# Relay_IO.net
KiCad netlist of a schematic drawn in Altium Designer
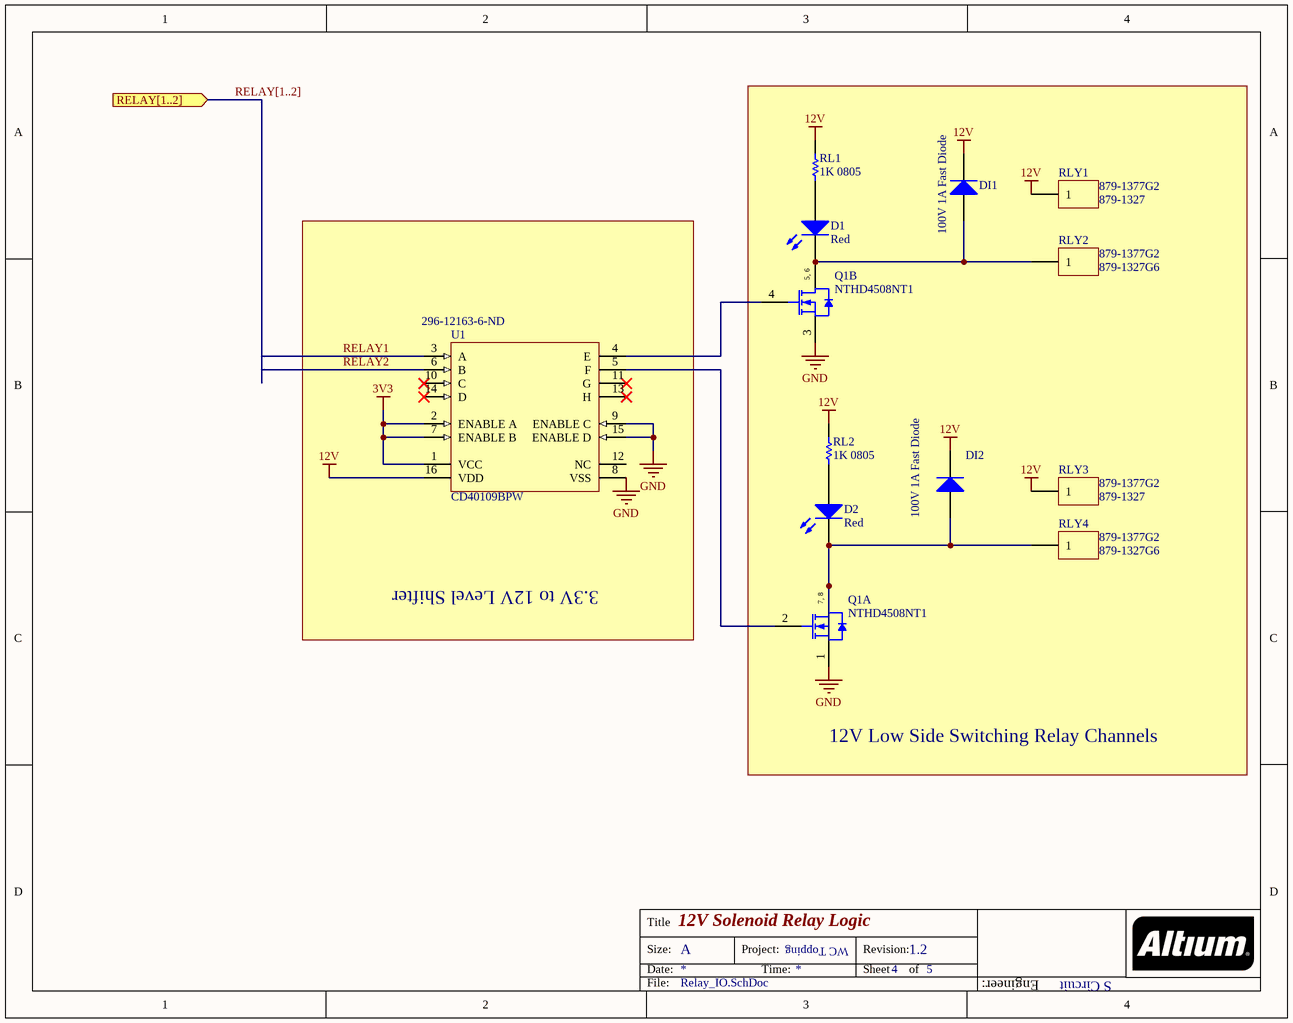
[diagram p0: Relay_IO.SchDoc]

(export (version "E")
  (design (tool "Eeschema 10.0.6"))
  (components
    (comp (ref "D1")
      (value "LED Red")
      (footprint "0603_A")
      (description "SMD mono-color Chip LED, WL-SMCW, Red")
      (fields
        (field (name "COLOR") "Red")
        (field (name "MANUFACTURER") "Wurth Electronics Inc")
        (field (name "MANUFACTURER PART NUMBER") "150060RS75000")
      )
      (libsource (lib "ICEdigikey") (part "LED_Red0603"))
    )
    (comp (ref "D2")
      (value "LED Red")
      (footprint "0603_A")
      (description "SMD mono-color Chip LED, WL-SMCW, Red")
      (fields
        (field (name "COLOR") "Red")
        (field (name "MANUFACTURER") "Wurth Electronics Inc")
        (field (name "MANUFACTURER PART NUMBER") "150060RS75000")
      )
      (libsource (lib "ICEdigikey") (part "LED_Red0603"))
    )
    (comp (ref "DI1")
      (value "100V 1A Fast Diode")
      (footprint "DO-35")
      (description "High Conductance Fast Diode")
      (fields
        (field (name "MANUFACTURER") "ON Semiconductor")
        (field (name "MANUFACTURER PART NUMBER") "MUR110RLG")
      )
      (libsource (lib "ICEdigikey") (part "Diode 1N4148"))
    )
    (comp (ref "DI2")
      (value "100V 1A Fast Diode")
      (footprint "DO-35")
      (description "High Conductance Fast Diode")
      (fields
        (field (name "MANUFACTURER") "ON Semiconductor")
        (field (name "MANUFACTURER PART NUMBER") "MUR110RLG")
      )
      (libsource (lib "ICEdigikey") (part "Diode 1N4148"))
    )
    (comp (ref "Q1")
      (value "NTHD4508NT1")
      (footprint "ONSC-CHIPFET-8-1206A-03_S2_V")
      (description "Power MOSFET, 20 V, 4.1 A, Dual N-Channel, 8-Pin CHIPFET, Tape and Reel")
      (fields
        (field (name "MANUFACTURER") "On Semiconductor")
        (field (name "MANUFACTURER PART NUMBER") "NTHD4508NT1G")
      )
      (libsource (lib "ICEdigikey") (part "NTHD4508NT1"))
    )
    (comp (ref "RL1")
      (value "1K 0805")
      (footprint "0805_L")
      (fields
        (field (name "MANUFACTURER") "Panasonic Electronic Components")
        (field (name "MANUFACTURER PART NUMBER") "ERJ-6GEYJ102V")
        (field (name "TOLERANCE") "±5%")
      )
      (libsource (lib "ICEdigikey") (part "Res1K_0805"))
    )
    (comp (ref "RL2")
      (value "1K 0805")
      (footprint "0805_L")
      (fields
        (field (name "MANUFACTURER") "Panasonic Electronic Components")
        (field (name "MANUFACTURER PART NUMBER") "ERJ-6GEYJ102V")
        (field (name "TOLERANCE") "±5%")
      )
      (libsource (lib "ICEdigikey") (part "Res1K_0805"))
    )
    (comp (ref "RLY1")
      (value "Anderson-1Pin RED_PCB_RHT")
      (footprint "Anderson_Red_RHT_BOT")
      (description "1 pin Anderson")
      (fields
        (field (name "MANUFACTURER") "Anderson Power Products (APP)")
        (field (name "MANUFACTURER PART NUMBER") "1377G1, 1377G2, 1327-BK,137G6-BK")
        (field (name "SUPPLIER PART NUMBER 1") "879-1377G2")
        (field (name "SUPPLIER PART NUMBER 2") "879-1327")
      )
      (libsource (lib "WCT") (part "Anderson-1Pin RED_PCB_RHT"))
    )
    (comp (ref "RLY2")
      (value "Anderson-1Pin BLK_PCB_RHT")
      (footprint "Anderson_BLK_RHT_BOT")
      (description "1 pin Anderson")
      (fields
        (field (name "MANUFACTURER") "Anderson Power Products (APP)")
        (field (name "MANUFACTURER PART NUMBER") "1377G1, 1377G2, 1327-BK,137G6-BK")
        (field (name "SUPPLIER PART NUMBER 1") "879-1377G2")
        (field (name "SUPPLIER PART NUMBER 2") "879-1327G6")
      )
      (libsource (lib "WCT") (part "Anderson-1Pin BLK_PCB_RHT"))
    )
    (comp (ref "RLY3")
      (value "Anderson-1Pin RED_PCB_RHT")
      (footprint "Anderson_Red_RHT_BOT")
      (description "1 pin Anderson")
      (fields
        (field (name "MANUFACTURER") "Anderson Power Products (APP)")
        (field (name "MANUFACTURER PART NUMBER") "1377G1, 1377G2, 1327-BK,137G6-BK")
        (field (name "SUPPLIER PART NUMBER 1") "879-1377G2")
        (field (name "SUPPLIER PART NUMBER 2") "879-1327")
      )
      (libsource (lib "WCT") (part "Anderson-1Pin RED_PCB_RHT"))
    )
    (comp (ref "RLY4")
      (value "Anderson-1Pin BLK_PCB_RHT")
      (footprint "Anderson_BLK_RHT_BOT")
      (description "1 pin Anderson")
      (fields
        (field (name "MANUFACTURER") "Anderson Power Products (APP)")
        (field (name "MANUFACTURER PART NUMBER") "1377G1, 1377G2, 1327-BK,137G6-BK")
        (field (name "SUPPLIER PART NUMBER 1") "879-1377G2")
        (field (name "SUPPLIER PART NUMBER 2") "879-1327G6")
      )
      (libsource (lib "WCT") (part "Anderson-1Pin BLK_PCB_RHT"))
    )
    (comp (ref "U1")
      (value "CD40109BPW")
      (footprint "PW0016A_M")
      (fields
        (field (name "MANUFACTURER") "Texas Instruments")
        (field (name "SUPPLIER PART NUMBER 1") "296-12163-6-ND")
        (field (name "MANUFACTURER PART NUMBER") "CD40109BPWR")
      )
      (libsource (lib "Altium Content Vault") (part "CMP-1527-00010-2"))
    )
  )
  (nets
    (net (code "1") (name "/RELAY1") (class "Default")
      (node (ref "U1") (pin "3") (pinfunction "A_3") (pintype "input"))
    )
    (net (code "2") (name "/RELAY2") (class "Default")
      (node (ref "U1") (pin "6") (pinfunction "B_6") (pintype "input"))
    )
    (net (code "4") (name "3V3") (class "Default")
      (node (ref "U1") (pin "1") (pinfunction "VCC_1") (pintype "power_in"))
      (node (ref "U1") (pin "2") (pinfunction "ENABLE_A_2") (pintype "input"))
      (node (ref "U1") (pin "7") (pinfunction "ENABLE_B_7") (pintype "input"))
    )
    (net (code "5") (name "12V") (class "Default")
      (node (ref "DI1") (pin "2") (pinfunction "K_2") (pintype "passive"))
      (node (ref "DI2") (pin "2") (pinfunction "K_2") (pintype "passive"))
      (node (ref "RL1") (pin "2") (pinfunction "2_2") (pintype "passive"))
      (node (ref "RL2") (pin "2") (pinfunction "2_2") (pintype "passive"))
      (node (ref "RLY1") (pin "1") (pinfunction "1_1") (pintype "passive"))
      (node (ref "RLY3") (pin "1") (pinfunction "1_1") (pintype "passive"))
      (node (ref "U1") (pin "16") (pinfunction "VDD_16") (pintype "power_in"))
    )
    (net (code "6") (name "GND") (class "Default")
      (node (ref "Q1") (pin "1") (pinfunction "S1_1") (pintype "passive"))
      (node (ref "Q1") (pin "3") (pinfunction "S2_3") (pintype "passive"))
      (node (ref "U1") (pin "15") (pinfunction "ENABLE_D_15") (pintype "input"))
      (node (ref "U1") (pin "8") (pinfunction "VSS_8") (pintype "power_in"))
      (node (ref "U1") (pin "9") (pinfunction "ENABLE_C_9") (pintype "input"))
    )
    (net (code "7") (name "Net-(D1-A)") (class "Default")
      (node (ref "D1") (pin "2") (pinfunction "A_2") (pintype "passive"))
      (node (ref "RL1") (pin "1") (pinfunction "1_1") (pintype "passive"))
    )
    (net (code "8") (name "Net-(D1-K)") (class "Default")
      (node (ref "D1") (pin "1") (pinfunction "K_1") (pintype "passive"))
      (node (ref "DI1") (pin "1") (pinfunction "A_1") (pintype "passive"))
      (node (ref "Q1") (pin "5") (pinfunction "D2_5") (pintype "passive"))
      (node (ref "Q1") (pin "6") (pinfunction "D2_6") (pintype "passive"))
      (node (ref "RLY2") (pin "1") (pinfunction "1_1") (pintype "passive"))
    )
    (net (code "9") (name "Net-(D2-A)") (class "Default")
      (node (ref "D2") (pin "2") (pinfunction "A_2") (pintype "passive"))
      (node (ref "RL2") (pin "1") (pinfunction "1_1") (pintype "passive"))
    )
    (net (code "10") (name "Net-(D2-K)") (class "Default")
      (node (ref "D2") (pin "1") (pinfunction "K_1") (pintype "passive"))
      (node (ref "DI2") (pin "1") (pinfunction "A_1") (pintype "passive"))
      (node (ref "Q1") (pin "7") (pinfunction "D1_7") (pintype "passive"))
      (node (ref "Q1") (pin "8") (pinfunction "D1_8") (pintype "passive"))
      (node (ref "RLY4") (pin "1") (pinfunction "1_1") (pintype "passive"))
    )
    (net (code "11") (name "Net-(Q1A-G1)") (class "Default")
      (node (ref "Q1") (pin "2") (pinfunction "G1_2") (pintype "passive"))
      (node (ref "U1") (pin "5") (pinfunction "F_5") (pintype "tri_state"))
    )
    (net (code "12") (name "Net-(Q1B-G2)") (class "Default")
      (node (ref "Q1") (pin "4") (pinfunction "G2_4") (pintype "passive"))
      (node (ref "U1") (pin "4") (pinfunction "E_4") (pintype "tri_state"))
    )
    (net (code "13") (name "unconnected-(U1-C-Pad10)") (class "Default")
      (node (ref "U1") (pin "10") (pinfunction "C_10") (pintype "input+no_connect"))
    )
    (net (code "14") (name "unconnected-(U1-D-Pad14)") (class "Default")
      (node (ref "U1") (pin "14") (pinfunction "D_14") (pintype "input+no_connect"))
    )
    (net (code "15") (name "unconnected-(U1-G-Pad11)") (class "Default")
      (node (ref "U1") (pin "11") (pinfunction "G_11") (pintype "tri_state+no_connect"))
    )
    (net (code "16") (name "unconnected-(U1-H-Pad13)") (class "Default")
      (node (ref "U1") (pin "13") (pinfunction "H_13") (pintype "tri_state+no_connect"))
    )
    (net (code "17") (name "unconnected-(U1-NC-Pad12)") (class "Default")
      (node (ref "U1") (pin "12") (pinfunction "NC_12") (pintype "passive"))
    )
  )
)
